# STM32F072.net
KiCad netlist of a schematic drawn in Altium Designer
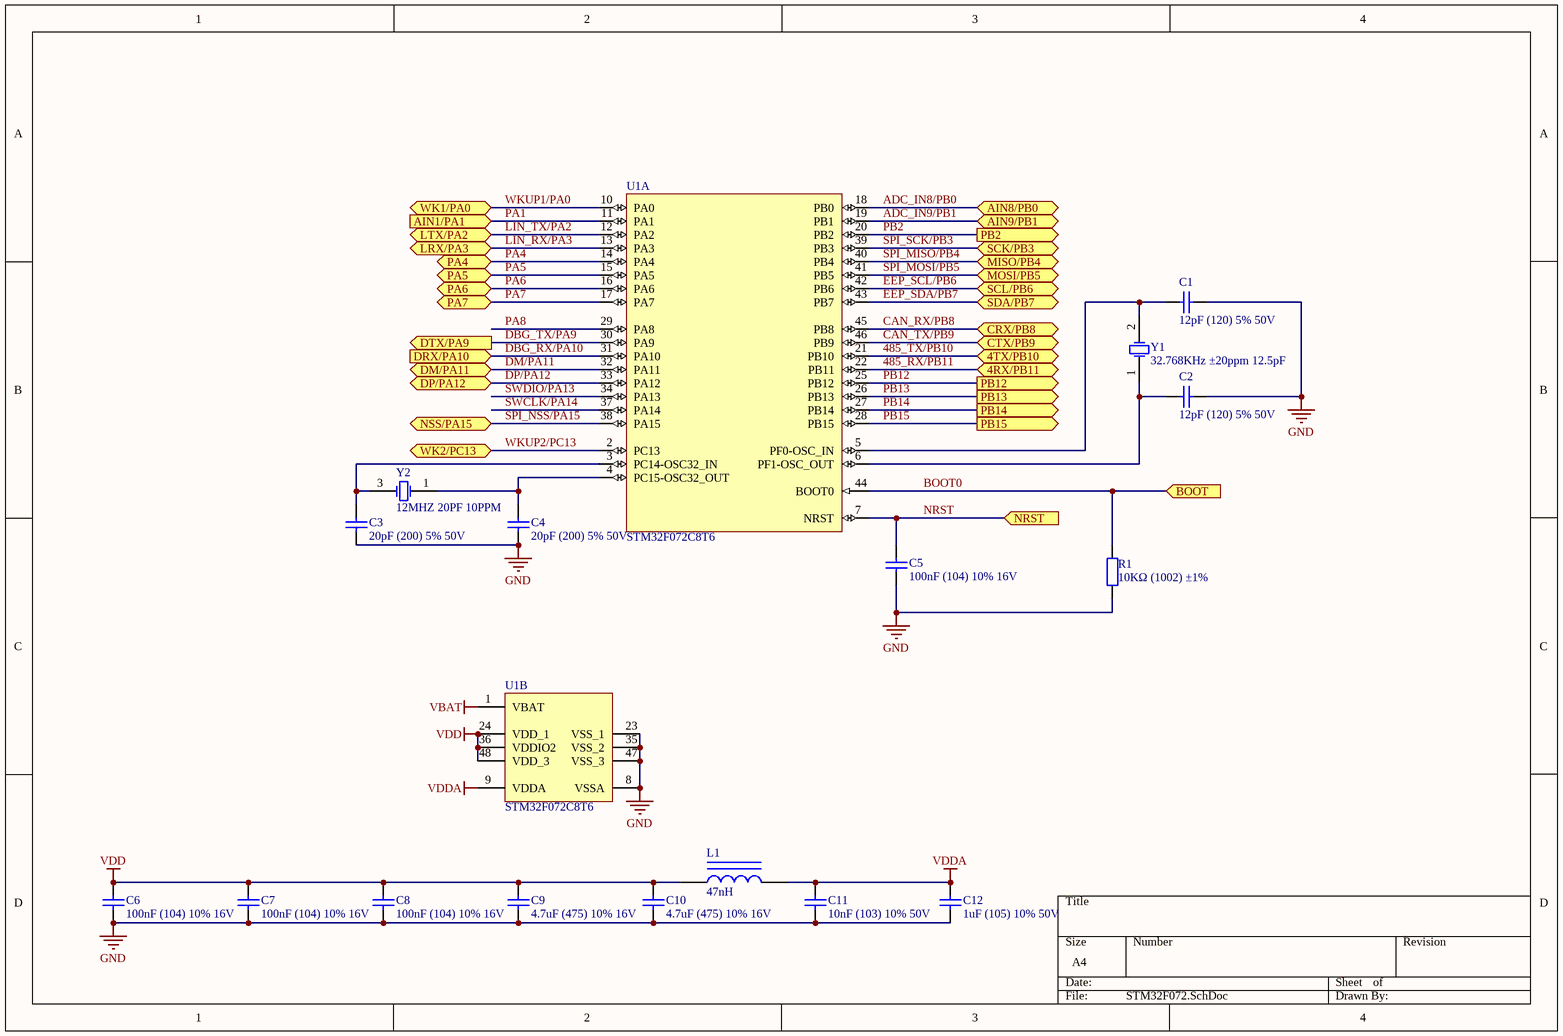
[diagram p0: STM32F072.SchDoc]

(export (version "E")
  (design (tool "Eeschema 10.0.6"))
  (components
    (comp (ref "C1")
      (value "12pF (120) 5% 50V")
      (footprint "0402_C")
      (description "贴片电容")
      (libsource (lib "Miscellaneous Devices LC") (part "0402 12pF (120) 5% 50V"))
    )
    (comp (ref "C2")
      (value "12pF (120) 5% 50V")
      (footprint "0402_C")
      (description "贴片电容")
      (libsource (lib "Miscellaneous Devices LC") (part "0402 12pF (120) 5% 50V"))
    )
    (comp (ref "C3")
      (value "20pF (200) 5% 50V")
      (footprint "0402_C")
      (description "贴片电容")
      (libsource (lib "Miscellaneous Devices LC") (part "0402 20pF (200) 5% 50V"))
    )
    (comp (ref "C4")
      (value "20pF (200) 5% 50V")
      (footprint "0402_C")
      (description "贴片电容")
      (libsource (lib "Miscellaneous Devices LC") (part "0402 20pF (200) 5% 50V"))
    )
    (comp (ref "C5")
      (value "100nF (104) 10% 16V")
      (footprint "0402_C")
      (description "贴片电容")
      (libsource (lib "Miscellaneous Devices LC") (part "0402 100nF (104) 10% 16V"))
    )
    (comp (ref "C6")
      (value "100nF (104) 10% 16V")
      (footprint "0402_C")
      (description "贴片电容")
      (libsource (lib "Miscellaneous Devices LC") (part "0402 100nF (104) 10% 16V"))
    )
    (comp (ref "C7")
      (value "100nF (104) 10% 16V")
      (footprint "0402_C")
      (description "贴片电容")
      (libsource (lib "Miscellaneous Devices LC") (part "0402 100nF (104) 10% 16V"))
    )
    (comp (ref "C8")
      (value "100nF (104) 10% 16V")
      (footprint "0402_C")
      (description "贴片电容")
      (libsource (lib "Miscellaneous Devices LC") (part "0402 100nF (104) 10% 16V"))
    )
    (comp (ref "C9")
      (value "4.7uF (475) 10% 16V")
      (footprint "0603_C")
      (description "贴片电容")
      (libsource (lib "Miscellaneous Devices LC") (part "0603 4.7uF (475) 10% 16V"))
    )
    (comp (ref "C10")
      (value "4.7uF (475) 10% 16V")
      (footprint "0603_C")
      (description "贴片电容")
      (libsource (lib "Miscellaneous Devices LC") (part "0603 4.7uF (475) 10% 16V"))
    )
    (comp (ref "C11")
      (value "10nF (103) 10% 50V")
      (footprint "0402_C")
      (description "贴片电容")
      (libsource (lib "Miscellaneous Devices LC") (part "0402 10nF (103) 10% 50V"))
    )
    (comp (ref "C12")
      (value "1uF (105) 10% 50V")
      (footprint "0603_C")
      (description "贴片电容")
      (libsource (lib "Miscellaneous Devices LC") (part "0603 1uF (105) 10% 50V"))
    )
    (comp (ref "L1")
      (value "47nH")
      (footprint "0603_L")
      (description "贴片电感")
      (libsource (lib "Miscellaneous Devices LC") (part "0603 47nH"))
    )
    (comp (ref "R1")
      (value "10KΩ (1002) ±1%")
      (footprint "0603_R")
      (description "贴片电阻")
      (libsource (lib "Miscellaneous Devices LC") (part "0603 10KΩ (1002) 1%"))
    )
    (comp (ref "U1")
      (value "STM32F072C8T6")
      (footprint "LQFP-48_7x7x05P")
      (description "ARM")
      (fields (field (name "COMMENT_1") "STM32F072C8T6"))
      (libsource (lib "Temp") (part "STM32F072C8T6"))
    )
    (comp (ref "Y1")
      (value "32.768KHz ±20ppm 12.5pF")
      (footprint "SMD-3215_2P FC - 135")
      (description "贴片晶振")
      (libsource (lib "Miscellaneous Devices LC") (part "SMD-3215_2P 32.768KHz 20ppm 12.5pF"))
    )
    (comp (ref "Y2")
      (value "12MHZ 20PF 10PPM")
      (footprint "SMD-3225_4P")
      (description "贴片晶振")
      (libsource (lib "Miscellaneous Devices LC") (part "SMD-3225_4P  12MHZ 20PF 10PPM"))
    )
  )
  (nets
    (net (code "1") (name "/485_RX{slash}PB11") (class "Default")
      (node (ref "U1") (pin "22") (pinfunction "PB11_22") (pintype "bidirectional"))
    )
    (net (code "2") (name "/485_TX{slash}PB10") (class "Default")
      (node (ref "U1") (pin "21") (pinfunction "PB10_21") (pintype "bidirectional"))
    )
    (net (code "3") (name "/ADC_IN8{slash}PB0") (class "Default")
      (node (ref "U1") (pin "18") (pinfunction "PB0_18") (pintype "bidirectional"))
    )
    (net (code "4") (name "/ADC_IN9{slash}PB1") (class "Default")
      (node (ref "U1") (pin "19") (pinfunction "PB1_19") (pintype "bidirectional"))
    )
    (net (code "5") (name "/BOOT0") (class "Default")
      (node (ref "R1") (pin "2") (pinfunction "2_2") (pintype "passive"))
      (node (ref "U1") (pin "44") (pinfunction "BOOT0_44") (pintype "input"))
    )
    (net (code "6") (name "/CAN_RX{slash}PB8") (class "Default")
      (node (ref "U1") (pin "45") (pinfunction "PB8_45") (pintype "bidirectional"))
    )
    (net (code "7") (name "/CAN_TX{slash}PB9") (class "Default")
      (node (ref "U1") (pin "46") (pinfunction "PB9_46") (pintype "bidirectional"))
    )
    (net (code "8") (name "/DBG_RX{slash}PA10") (class "Default")
      (node (ref "U1") (pin "31") (pinfunction "PA10_31") (pintype "bidirectional"))
    )
    (net (code "9") (name "/DBG_TX{slash}PA9") (class "Default")
      (node (ref "U1") (pin "30") (pinfunction "PA9_30") (pintype "bidirectional"))
    )
    (net (code "10") (name "/DM{slash}PA11") (class "Default")
      (node (ref "U1") (pin "32") (pinfunction "PA11_32") (pintype "bidirectional"))
    )
    (net (code "11") (name "/DP{slash}PA12") (class "Default")
      (node (ref "U1") (pin "33") (pinfunction "PA12_33") (pintype "bidirectional"))
    )
    (net (code "12") (name "/EEP_SCL{slash}PB6") (class "Default")
      (node (ref "U1") (pin "42") (pinfunction "PB6_42") (pintype "bidirectional"))
    )
    (net (code "13") (name "/EEP_SDA{slash}PB7") (class "Default")
      (node (ref "U1") (pin "43") (pinfunction "PB7_43") (pintype "bidirectional"))
    )
    (net (code "14") (name "/LIN_RX{slash}PA3") (class "Default")
      (node (ref "U1") (pin "13") (pinfunction "PA3_13") (pintype "bidirectional"))
    )
    (net (code "15") (name "/LIN_TX{slash}PA2") (class "Default")
      (node (ref "U1") (pin "12") (pinfunction "PA2_12") (pintype "bidirectional"))
    )
    (net (code "16") (name "/NRST") (class "Default")
      (node (ref "C5") (pin "2") (pinfunction "2_2") (pintype "passive"))
      (node (ref "U1") (pin "7") (pinfunction "NRST_7") (pintype "bidirectional"))
    )
    (net (code "17") (name "/PA1") (class "Default")
      (node (ref "U1") (pin "11") (pinfunction "PA1_11") (pintype "bidirectional"))
    )
    (net (code "18") (name "/PA4") (class "Default")
      (node (ref "U1") (pin "14") (pinfunction "PA4_14") (pintype "bidirectional"))
    )
    (net (code "19") (name "/PA5") (class "Default")
      (node (ref "U1") (pin "15") (pinfunction "PA5_15") (pintype "bidirectional"))
    )
    (net (code "20") (name "/PA6") (class "Default")
      (node (ref "U1") (pin "16") (pinfunction "PA6_16") (pintype "bidirectional"))
    )
    (net (code "21") (name "/PA7") (class "Default")
      (node (ref "U1") (pin "17") (pinfunction "PA7_17") (pintype "bidirectional"))
    )
    (net (code "22") (name "/PA8") (class "Default")
      (node (ref "U1") (pin "29") (pinfunction "PA8_29") (pintype "bidirectional"))
    )
    (net (code "23") (name "/PB2") (class "Default")
      (node (ref "U1") (pin "20") (pinfunction "PB2_20") (pintype "bidirectional"))
    )
    (net (code "24") (name "/PB12") (class "Default")
      (node (ref "U1") (pin "25") (pinfunction "PB12_25") (pintype "bidirectional"))
    )
    (net (code "25") (name "/PB13") (class "Default")
      (node (ref "U1") (pin "26") (pinfunction "PB13_26") (pintype "bidirectional"))
    )
    (net (code "26") (name "/PB14") (class "Default")
      (node (ref "U1") (pin "27") (pinfunction "PB14_27") (pintype "bidirectional"))
    )
    (net (code "27") (name "/PB15") (class "Default")
      (node (ref "U1") (pin "28") (pinfunction "PB15_28") (pintype "bidirectional"))
    )
    (net (code "28") (name "/SPI_MISO{slash}PB4") (class "Default")
      (node (ref "U1") (pin "40") (pinfunction "PB4_40") (pintype "bidirectional"))
    )
    (net (code "29") (name "/SPI_MOSI{slash}PB5") (class "Default")
      (node (ref "U1") (pin "41") (pinfunction "PB5_41") (pintype "bidirectional"))
    )
    (net (code "30") (name "/SPI_NSS{slash}PA15") (class "Default")
      (node (ref "U1") (pin "38") (pinfunction "PA15_38") (pintype "bidirectional"))
    )
    (net (code "31") (name "/SPI_SCK{slash}PB3") (class "Default")
      (node (ref "U1") (pin "39") (pinfunction "PB3_39") (pintype "bidirectional"))
    )
    (net (code "32") (name "/SWCLK{slash}PA14") (class "Default")
      (node (ref "U1") (pin "37") (pinfunction "PA14_37") (pintype "bidirectional"))
    )
    (net (code "33") (name "/SWDIO{slash}PA13") (class "Default")
      (node (ref "U1") (pin "34") (pinfunction "PA13_34") (pintype "bidirectional"))
    )
    (net (code "34") (name "/WKUP1{slash}PA0") (class "Default")
      (node (ref "U1") (pin "10") (pinfunction "PA0_10") (pintype "bidirectional"))
    )
    (net (code "35") (name "/WKUP2{slash}PC13") (class "Default")
      (node (ref "U1") (pin "2") (pinfunction "PC13_2") (pintype "bidirectional"))
    )
    (net (code "36") (name "GND") (class "Default")
      (node (ref "C1") (pin "2") (pinfunction "2_2") (pintype "passive"))
      (node (ref "C10") (pin "1") (pinfunction "1_1") (pintype "passive"))
      (node (ref "C11") (pin "2") (pinfunction "2_2") (pintype "passive"))
      (node (ref "C12") (pin "2") (pinfunction "2_2") (pintype "passive"))
      (node (ref "C2") (pin "2") (pinfunction "2_2") (pintype "passive"))
      (node (ref "C3") (pin "1") (pinfunction "1_1") (pintype "passive"))
      (node (ref "C4") (pin "1") (pinfunction "1_1") (pintype "passive"))
      (node (ref "C5") (pin "1") (pinfunction "1_1") (pintype "passive"))
      (node (ref "C6") (pin "1") (pinfunction "1_1") (pintype "passive"))
      (node (ref "C7") (pin "1") (pinfunction "1_1") (pintype "passive"))
      (node (ref "C8") (pin "1") (pinfunction "1_1") (pintype "passive"))
      (node (ref "C9") (pin "1") (pinfunction "1_1") (pintype "passive"))
      (node (ref "R1") (pin "1") (pinfunction "1_1") (pintype "passive"))
      (node (ref "U1") (pin "23") (pinfunction "VSS_1_23") (pintype "power_in"))
      (node (ref "U1") (pin "35") (pinfunction "VSS_2_35") (pintype "power_in"))
      (node (ref "U1") (pin "47") (pinfunction "VSS_3_47") (pintype "power_in"))
      (node (ref "U1") (pin "8") (pinfunction "VSSA_8") (pintype "power_in"))
    )
    (net (code "37") (name "Net-(U1A-PC14-OSC32_IN)") (class "Default")
      (node (ref "C3") (pin "2") (pinfunction "2_2") (pintype "passive"))
      (node (ref "U1") (pin "3") (pinfunction "PC14-OSC32_IN_3") (pintype "bidirectional"))
      (node (ref "Y2") (pin "3") (pinfunction "OSC2_3") (pintype "passive"))
    )
    (net (code "38") (name "Net-(U1A-PC15-OSC32_OUT)") (class "Default")
      (node (ref "C4") (pin "2") (pinfunction "2_2") (pintype "passive"))
      (node (ref "U1") (pin "4") (pinfunction "PC15-OSC32_OUT_4") (pintype "bidirectional"))
      (node (ref "Y2") (pin "1") (pinfunction "OSC1_1") (pintype "passive"))
    )
    (net (code "39") (name "Net-(U1A-PF0-OSC_IN)") (class "Default")
      (node (ref "C1") (pin "1") (pinfunction "1_1") (pintype "passive"))
      (node (ref "U1") (pin "5") (pinfunction "PF0-OSC_IN_5") (pintype "bidirectional"))
      (node (ref "Y1") (pin "2") (pinfunction "OSC2_2") (pintype "passive"))
    )
    (net (code "40") (name "Net-(U1A-PF1-OSC_OUT)") (class "Default")
      (node (ref "C2") (pin "1") (pinfunction "1_1") (pintype "passive"))
      (node (ref "U1") (pin "6") (pinfunction "PF1-OSC_OUT_6") (pintype "bidirectional"))
      (node (ref "Y1") (pin "1") (pinfunction "OSC1_1") (pintype "passive"))
    )
    (net (code "41") (name "VBAT") (class "Default")
      (node (ref "U1") (pin "1") (pinfunction "VBAT_1") (pintype "power_in"))
    )
    (net (code "42") (name "VDD") (class "Default")
      (node (ref "C10") (pin "2") (pinfunction "2_2") (pintype "passive"))
      (node (ref "C6") (pin "2") (pinfunction "2_2") (pintype "passive"))
      (node (ref "C7") (pin "2") (pinfunction "2_2") (pintype "passive"))
      (node (ref "C8") (pin "2") (pinfunction "2_2") (pintype "passive"))
      (node (ref "C9") (pin "2") (pinfunction "2_2") (pintype "passive"))
      (node (ref "L1") (pin "1") (pinfunction "1_1") (pintype "passive"))
      (node (ref "U1") (pin "24") (pinfunction "VDD_1_24") (pintype "power_in"))
      (node (ref "U1") (pin "36") (pinfunction "VDDIO2_36") (pintype "power_in"))
      (node (ref "U1") (pin "48") (pinfunction "VDD_3_48") (pintype "power_in"))
    )
    (net (code "43") (name "VDDA") (class "Default")
      (node (ref "C11") (pin "1") (pinfunction "1_1") (pintype "passive"))
      (node (ref "C12") (pin "1") (pinfunction "1_1") (pintype "passive"))
      (node (ref "L1") (pin "2") (pinfunction "2_2") (pintype "passive"))
      (node (ref "U1") (pin "9") (pinfunction "VDDA_9") (pintype "power_in"))
    )
  )
)
